# GATE_DRIVER_BOARD.net
KiCad netlist of a schematic drawn in Altium Designer
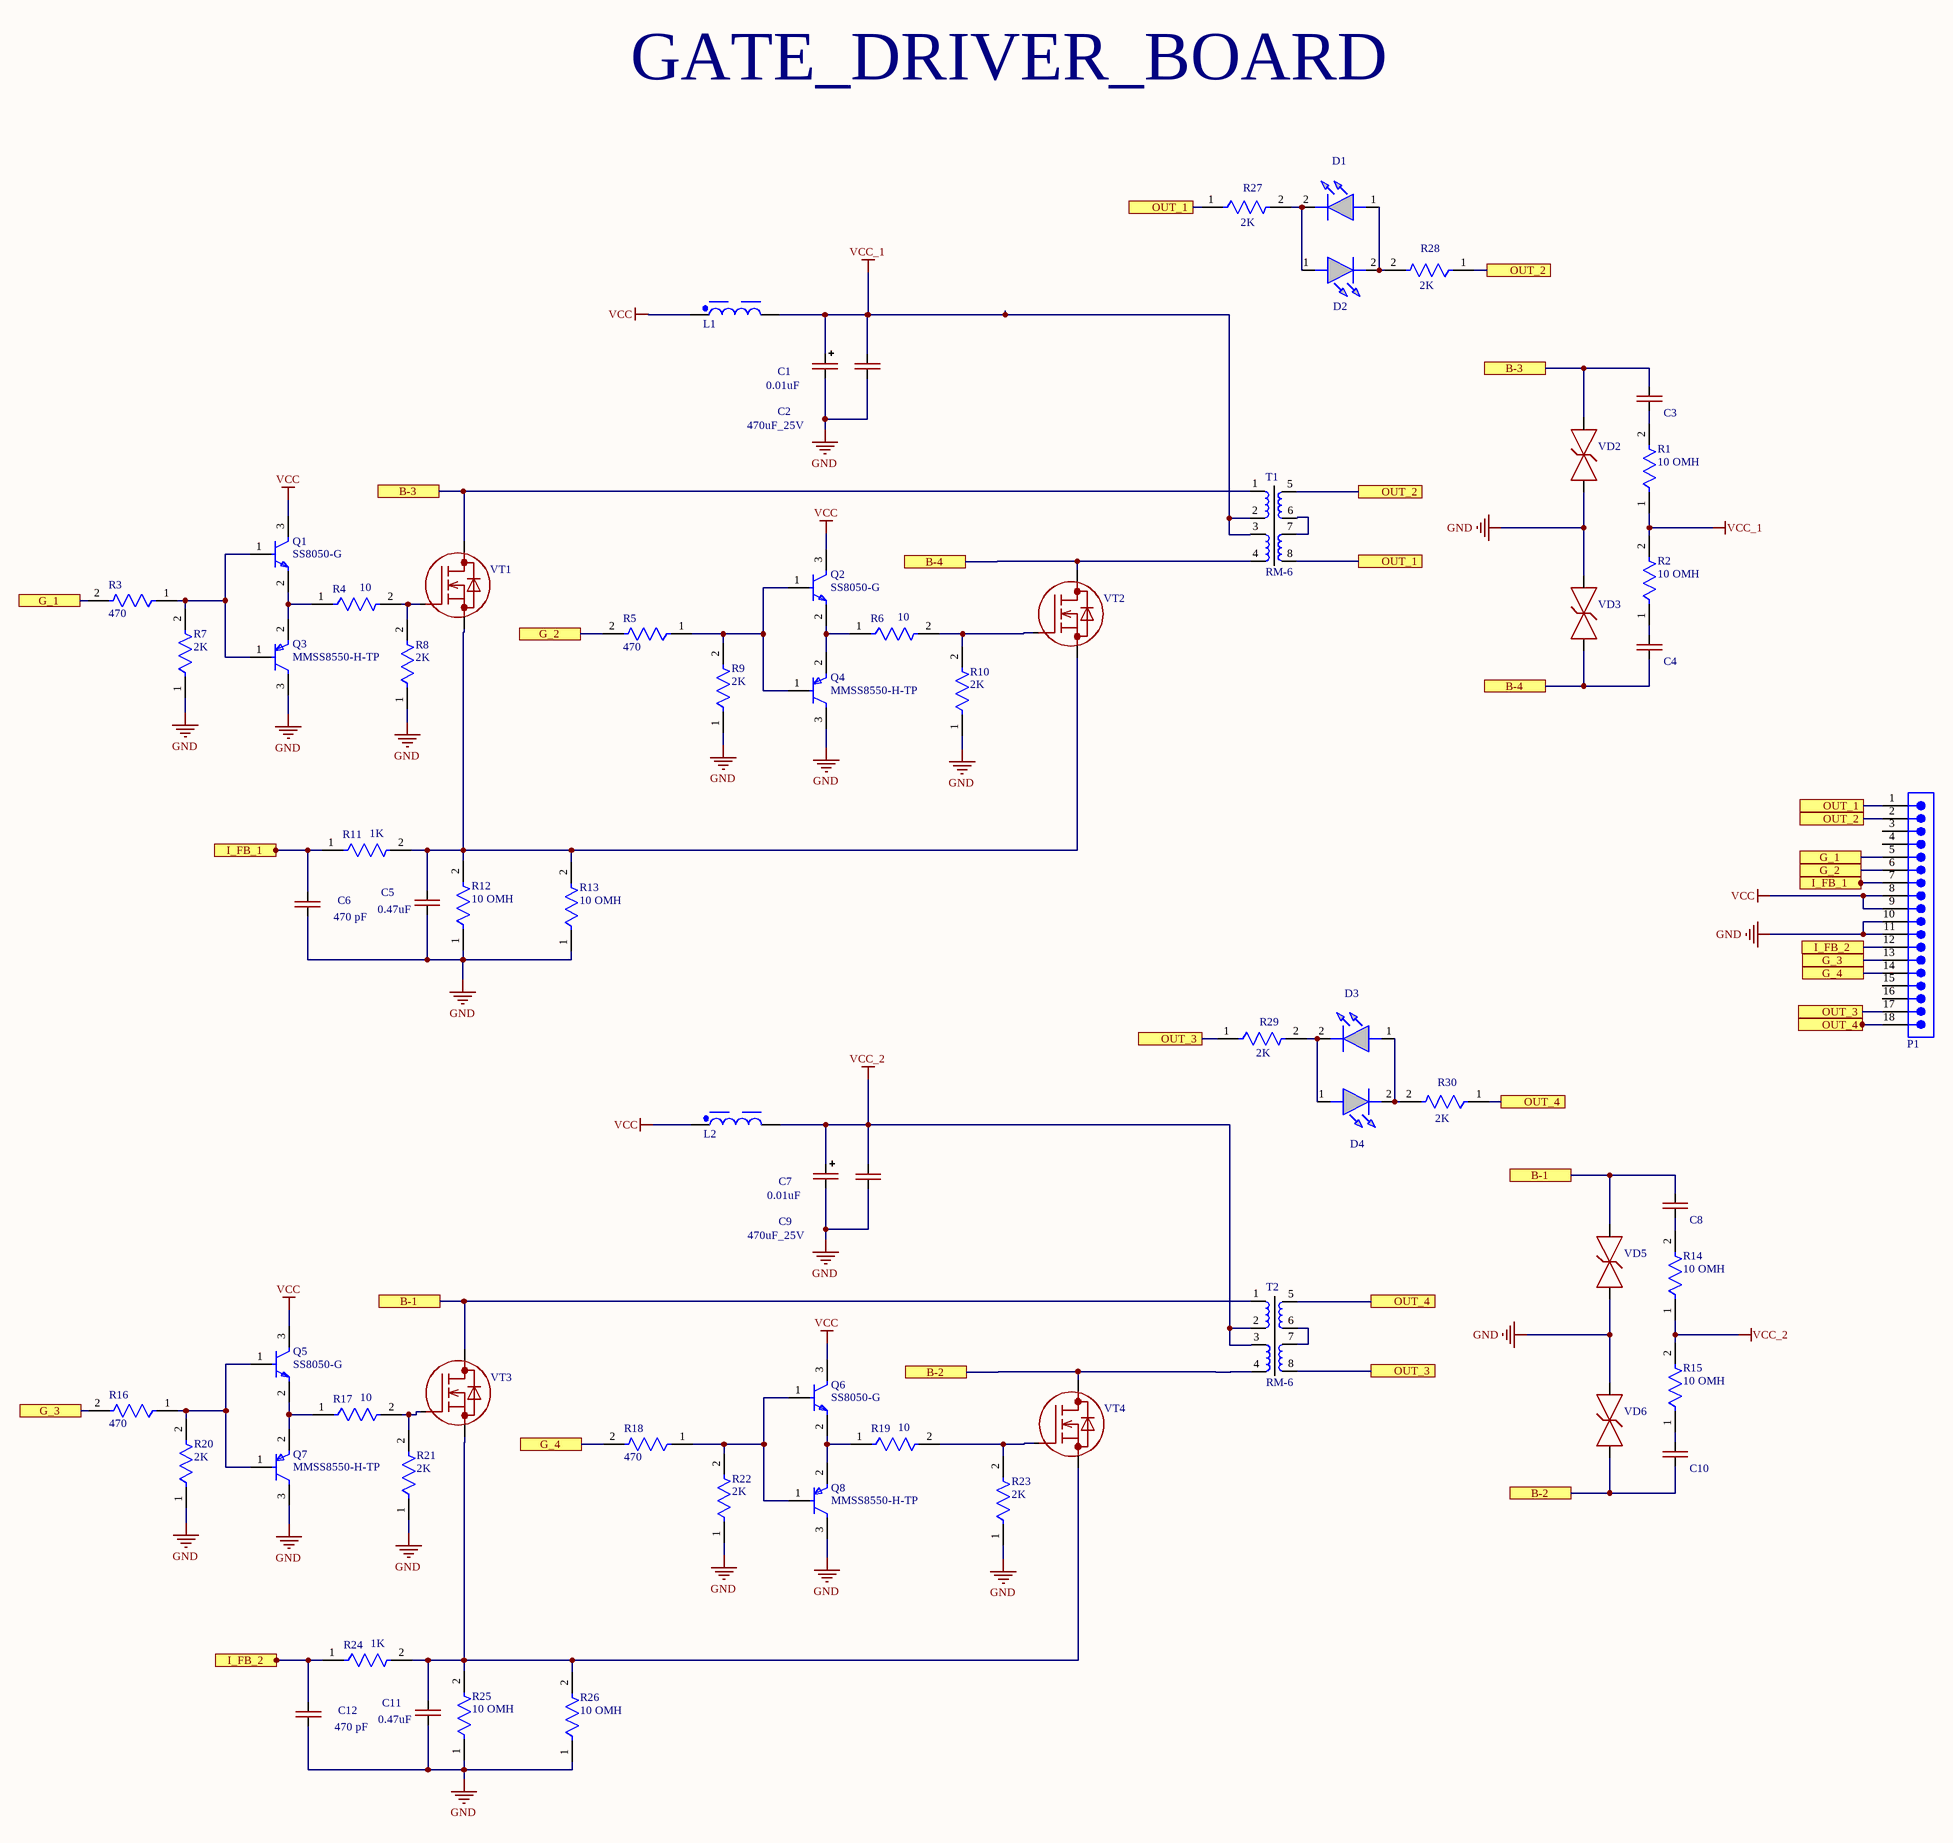
[diagram p0: GATE_DRIVER_BOARD.SchDoc]

(export (version "E")
  (design (tool "Eeschema 10.0.6"))
  (components
    (comp (ref "C1")
      (value "0.01uF")
      (footprint "CAP-0805")
      (libsource (lib "PASSIVE_COMPONENTS") (part "CAP-NON-POLAR"))
    )
    (comp (ref "C2")
      (value "470uF_25V")
      (footprint "CAP_SMD_Size_G")
      (libsource (lib "PASSIVE_COMPONENTS") (part "CAP-POLAR"))
    )
    (comp (ref "C3")
      (value "CAP-V")
      (footprint "CAP-V")
      (libsource (lib "PASSIVE_COMPONENTS") (part "CAP-V"))
    )
    (comp (ref "C4")
      (value "CAP-V")
      (footprint "CAP-V")
      (libsource (lib "PASSIVE_COMPONENTS") (part "CAP-V"))
    )
    (comp (ref "C5")
      (value "0.47uF")
      (footprint "CAP-0805")
      (libsource (lib "PASSIVE_COMPONENTS") (part "CAP-NON-POLAR"))
    )
    (comp (ref "C6")
      (value "470 pF")
      (footprint "CAP-0805")
      (libsource (lib "PASSIVE_COMPONENTS") (part "CAP-NON-POLAR"))
    )
    (comp (ref "C7")
      (value "0.01uF")
      (footprint "CAP-0805")
      (libsource (lib "PASSIVE_COMPONENTS") (part "CAP-NON-POLAR"))
    )
    (comp (ref "C8")
      (value "CAP-V")
      (footprint "CAP-V")
      (libsource (lib "PASSIVE_COMPONENTS") (part "CAP-V"))
    )
    (comp (ref "C9")
      (value "470uF_25V")
      (footprint "CAP_SMD_Size_G")
      (libsource (lib "PASSIVE_COMPONENTS") (part "CAP-POLAR"))
    )
    (comp (ref "C10")
      (value "CAP-V")
      (footprint "CAP-V")
      (libsource (lib "PASSIVE_COMPONENTS") (part "CAP-V"))
    )
    (comp (ref "C11")
      (value "0.47uF")
      (footprint "CAP-0805")
      (libsource (lib "PASSIVE_COMPONENTS") (part "CAP-NON-POLAR"))
    )
    (comp (ref "C12")
      (value "470 pF")
      (footprint "CAP-0805")
      (libsource (lib "PASSIVE_COMPONENTS") (part "CAP-NON-POLAR"))
    )
    (comp (ref "D1")
      (value "151031YS06000")
      (footprint "LED_RED")
      (description "WURTH ELEKTRONIK - 151031YS06000 - LED, Yellow, Through Hole, T-1 (3mm), 30 mA, 2 V, 590 nm")
      (fields (field (name "MOUSER PART NUMBER") "710-151031YS06000"))
      (libsource (lib "Optic-LED") (part "LED"))
    )
    (comp (ref "D2")
      (value "151031YS06000")
      (footprint "LED_RED")
      (description "WURTH ELEKTRONIK - 151031YS06000 - LED, Yellow, Through Hole, T-1 (3mm), 30 mA, 2 V, 590 nm")
      (fields (field (name "MOUSER PART NUMBER") "710-151031YS06000"))
      (libsource (lib "Optic-LED") (part "LED"))
    )
    (comp (ref "D3")
      (value "151031YS06000")
      (footprint "LED_RED")
      (description "WURTH ELEKTRONIK - 151031YS06000 - LED, Yellow, Through Hole, T-1 (3mm), 30 mA, 2 V, 590 nm")
      (fields (field (name "MOUSER PART NUMBER") "710-151031YS06000"))
      (libsource (lib "Optic-LED") (part "LED"))
    )
    (comp (ref "D4")
      (value "151031YS06000")
      (footprint "LED_RED")
      (description "WURTH ELEKTRONIK - 151031YS06000 - LED, Yellow, Through Hole, T-1 (3mm), 30 mA, 2 V, 590 nm")
      (fields (field (name "MOUSER PART NUMBER") "710-151031YS06000"))
      (libsource (lib "Optic-LED") (part "LED"))
    )
    (comp (ref "L1")
      (value "390µH, 0.38A")
      (footprint "WE-PD2_7850")
      (description "WE-PD2 SMT Power Inductor, size 7850, 390µH, 0.38A, 1.77Ω")
      (fields
        (field (name "MANUFACTURER PART NUMBER") "744775239")
        (field (name "MANUFACTURER") "Wurth Elektronik")
      )
      (libsource (lib "WE-PD2 (rev22d)") (part "744775239"))
    )
    (comp (ref "L2")
      (value "390µH, 0.38A")
      (footprint "WE-PD2_7850")
      (description "WE-PD2 SMT Power Inductor, size 7850, 390µH, 0.38A, 1.77Ω")
      (fields
        (field (name "MANUFACTURER PART NUMBER") "744775239")
        (field (name "MANUFACTURER") "Wurth Elektronik")
      )
      (libsource (lib "WE-PD2 (rev22d)") (part "744775239"))
    )
    (comp (ref "P1")
      (value "61301811021")
      (footprint "61301811021")
      (description "WR-PHD Pin Header, THT, Angled, pitch 2.54mm, 1 Row, 18P")
      (fields (field (name "MANUFACTURER") "Wurth Elektronik"))
      (libsource (lib "Altium_WR-PHD (rev22b)") (part "61301811021"))
    )
    (comp (ref "Q1")
      (value "SS8050-G")
      (footprint "FP-SS8050-G-MFG")
      (description "NPN TRANSISTOR 1.5A 40V SOT-23 R")
      (libsource (lib "Altium Content Vault") (part "2a1388f82443b098dcd57d24ac7632d"))
    )
    (comp (ref "Q2")
      (value "SS8050-G")
      (footprint "FP-SS8050-G-MFG")
      (description "NPN TRANSISTOR 1.5A 40V SOT-23 R")
      (libsource (lib "Altium Content Vault") (part "2a1388f82443b098dcd57d24ac7632d"))
    )
    (comp (ref "Q3")
      (value "MMSS8550-H-TP")
      (footprint "FP-SOT-23-IPC_B")
      (description "TRANS PNP 25V 1.5A SOT23")
      (libsource (lib "Altium Content Vault") (part "0e8486ed3b47d9c69b8404ba87cf0f7"))
    )
    (comp (ref "Q4")
      (value "MMSS8550-H-TP")
      (footprint "FP-SOT-23-IPC_B")
      (description "TRANS PNP 25V 1.5A SOT23")
      (libsource (lib "Altium Content Vault") (part "0e8486ed3b47d9c69b8404ba87cf0f7"))
    )
    (comp (ref "Q5")
      (value "SS8050-G")
      (footprint "FP-SS8050-G-MFG")
      (description "NPN TRANSISTOR 1.5A 40V SOT-23 R")
      (libsource (lib "Altium Content Vault") (part "2a1388f82443b098dcd57d24ac7632d"))
    )
    (comp (ref "Q6")
      (value "SS8050-G")
      (footprint "FP-SS8050-G-MFG")
      (description "NPN TRANSISTOR 1.5A 40V SOT-23 R")
      (libsource (lib "Altium Content Vault") (part "2a1388f82443b098dcd57d24ac7632d"))
    )
    (comp (ref "Q7")
      (value "MMSS8550-H-TP")
      (footprint "FP-SOT-23-IPC_B")
      (description "TRANS PNP 25V 1.5A SOT23")
      (libsource (lib "Altium Content Vault") (part "0e8486ed3b47d9c69b8404ba87cf0f7"))
    )
    (comp (ref "Q8")
      (value "MMSS8550-H-TP")
      (footprint "FP-SOT-23-IPC_B")
      (description "TRANS PNP 25V 1.5A SOT23")
      (libsource (lib "Altium Content Vault") (part "0e8486ed3b47d9c69b8404ba87cf0f7"))
    )
    (comp (ref "R1")
      (value "10 OMH")
      (footprint "RES-1206")
      (libsource (lib "PASSIVE_COMPONENTS") (part "RES-CONST"))
    )
    (comp (ref "R2")
      (value "10 OMH")
      (footprint "RES-1206")
      (libsource (lib "PASSIVE_COMPONENTS") (part "RES-CONST"))
    )
    (comp (ref "R3")
      (value "470")
      (footprint "RES-0805")
      (libsource (lib "PASSIVE_COMPONENTS") (part "RES-CONST"))
    )
    (comp (ref "R4")
      (value "10")
      (footprint "RES-0805")
      (libsource (lib "PASSIVE_COMPONENTS") (part "RES-CONST"))
    )
    (comp (ref "R5")
      (value "470")
      (footprint "RES-0805")
      (libsource (lib "PASSIVE_COMPONENTS") (part "RES-CONST"))
    )
    (comp (ref "R6")
      (value "10")
      (footprint "RES-0805")
      (libsource (lib "PASSIVE_COMPONENTS") (part "RES-CONST"))
    )
    (comp (ref "R7")
      (value "2K")
      (footprint "RES-0805")
      (libsource (lib "PASSIVE_COMPONENTS") (part "RES-CONST"))
    )
    (comp (ref "R8")
      (value "2K")
      (footprint "RES-0805")
      (libsource (lib "PASSIVE_COMPONENTS") (part "RES-CONST"))
    )
    (comp (ref "R9")
      (value "2K")
      (footprint "RES-0805")
      (libsource (lib "PASSIVE_COMPONENTS") (part "RES-CONST"))
    )
    (comp (ref "R10")
      (value "2K")
      (footprint "RES-0805")
      (libsource (lib "PASSIVE_COMPONENTS") (part "RES-CONST"))
    )
    (comp (ref "R11")
      (value "1K")
      (footprint "RES-0805")
      (libsource (lib "PASSIVE_COMPONENTS") (part "RES-CONST"))
    )
    (comp (ref "R12")
      (value "10 OMH")
      (footprint "RES-2512")
      (libsource (lib "PASSIVE_COMPONENTS") (part "RES-CONST"))
    )
    (comp (ref "R13")
      (value "10 OMH")
      (footprint "RES-2512")
      (libsource (lib "PASSIVE_COMPONENTS") (part "RES-CONST"))
    )
    (comp (ref "R14")
      (value "10 OMH")
      (footprint "RES-1206")
      (libsource (lib "PASSIVE_COMPONENTS") (part "RES-CONST"))
    )
    (comp (ref "R15")
      (value "10 OMH")
      (footprint "RES-1206")
      (libsource (lib "PASSIVE_COMPONENTS") (part "RES-CONST"))
    )
    (comp (ref "R16")
      (value "470")
      (footprint "RES-0805")
      (libsource (lib "PASSIVE_COMPONENTS") (part "RES-CONST"))
    )
    (comp (ref "R17")
      (value "10")
      (footprint "RES-0805")
      (libsource (lib "PASSIVE_COMPONENTS") (part "RES-CONST"))
    )
    (comp (ref "R18")
      (value "470")
      (footprint "RES-0805")
      (libsource (lib "PASSIVE_COMPONENTS") (part "RES-CONST"))
    )
    (comp (ref "R19")
      (value "10")
      (footprint "RES-0805")
      (libsource (lib "PASSIVE_COMPONENTS") (part "RES-CONST"))
    )
    (comp (ref "R20")
      (value "2K")
      (footprint "RES-0805")
      (libsource (lib "PASSIVE_COMPONENTS") (part "RES-CONST"))
    )
    (comp (ref "R21")
      (value "2K")
      (footprint "RES-0805")
      (libsource (lib "PASSIVE_COMPONENTS") (part "RES-CONST"))
    )
    (comp (ref "R22")
      (value "2K")
      (footprint "RES-0805")
      (libsource (lib "PASSIVE_COMPONENTS") (part "RES-CONST"))
    )
    (comp (ref "R23")
      (value "2K")
      (footprint "RES-0805")
      (libsource (lib "PASSIVE_COMPONENTS") (part "RES-CONST"))
    )
    (comp (ref "R24")
      (value "1K")
      (footprint "RES-0805")
      (libsource (lib "PASSIVE_COMPONENTS") (part "RES-CONST"))
    )
    (comp (ref "R25")
      (value "10 OMH")
      (footprint "RES-2512")
      (libsource (lib "PASSIVE_COMPONENTS") (part "RES-CONST"))
    )
    (comp (ref "R26")
      (value "10 OMH")
      (footprint "RES-2512")
      (libsource (lib "PASSIVE_COMPONENTS") (part "RES-CONST"))
    )
    (comp (ref "R27")
      (value "2K")
      (footprint "RES-0805")
      (description "10K")
      (libsource (lib "PASSIVE_COMPONENTS") (part "RES-CONST"))
    )
    (comp (ref "R28")
      (value "2K")
      (footprint "RES-0805")
      (description "10K")
      (libsource (lib "PASSIVE_COMPONENTS") (part "RES-CONST"))
    )
    (comp (ref "R29")
      (value "2K")
      (footprint "RES-0805")
      (description "10K")
      (libsource (lib "PASSIVE_COMPONENTS") (part "RES-CONST"))
    )
    (comp (ref "R30")
      (value "2K")
      (footprint "RES-0805")
      (description "10K")
      (libsource (lib "PASSIVE_COMPONENTS") (part "RES-CONST"))
    )
    (comp (ref "T1")
      (value "RM-6")
      (footprint "TRANS_RM6")
      (libsource (lib "Transformers") (part "RM_6_12-12-18-18"))
    )
    (comp (ref "T2")
      (value "RM-6")
      (footprint "TRANS_RM6")
      (libsource (lib "Transformers") (part "RM_6_12-12-18-18"))
    )
    (comp (ref "VD2")
      (value "Suppressor")
      (footprint "P6KE350CA")
      (libsource (lib "Diodes") (part "Suppressor"))
    )
    (comp (ref "VD3")
      (value "Suppressor")
      (footprint "P6KE350CA")
      (libsource (lib "Diodes") (part "Suppressor"))
    )
    (comp (ref "VD5")
      (value "Suppressor")
      (footprint "P6KE350CA")
      (libsource (lib "Diodes") (part "Suppressor"))
    )
    (comp (ref "VD6")
      (value "Suppressor")
      (footprint "P6KE350CA")
      (libsource (lib "Diodes") (part "Suppressor"))
    )
    (comp (ref "VT1")
      (value "MOSFET-N-GDS")
      (footprint "TO-220-5")
      (libsource (lib "AOD514") (part "MOSFET-N-GDS"))
    )
    (comp (ref "VT2")
      (value "MOSFET-N-GDS")
      (footprint "TO-220-5")
      (libsource (lib "AOD514") (part "MOSFET-N-GDS"))
    )
    (comp (ref "VT3")
      (value "MOSFET-N-GDS")
      (footprint "TO-220-5")
      (libsource (lib "AOD514") (part "MOSFET-N-GDS"))
    )
    (comp (ref "VT4")
      (value "MOSFET-N-GDS")
      (footprint "TO-220-5")
      (libsource (lib "AOD514") (part "MOSFET-N-GDS"))
    )
  )
  (nets
    (net (code "1") (name "/B-1") (class "Default")
      (node (ref "C8") (pin "2") (pinfunction "2_2") (pintype "passive"))
      (node (ref "T2") (pin "1") (pinfunction "1_1") (pintype "passive"))
      (node (ref "VD5") (pin "2") (pinfunction "A_2") (pintype "passive"))
      (node (ref "VT3") (pin "2") (pinfunction "D_2") (pintype "passive"))
    )
    (net (code "2") (name "/B-2") (class "Default")
      (node (ref "C10") (pin "1") (pinfunction "1_1") (pintype "passive"))
      (node (ref "T2") (pin "4") (pinfunction "4_4") (pintype "passive"))
      (node (ref "VD6") (pin "1") (pinfunction "C_1") (pintype "passive"))
      (node (ref "VT4") (pin "2") (pinfunction "D_2") (pintype "passive"))
    )
    (net (code "3") (name "/B-3") (class "Default")
      (node (ref "C3") (pin "2") (pinfunction "2_2") (pintype "passive"))
      (node (ref "T1") (pin "1") (pinfunction "1_1") (pintype "passive"))
      (node (ref "VD2") (pin "2") (pinfunction "A_2") (pintype "passive"))
      (node (ref "VT1") (pin "2") (pinfunction "D_2") (pintype "passive"))
    )
    (net (code "4") (name "/B-4") (class "Default")
      (node (ref "C4") (pin "1") (pinfunction "1_1") (pintype "passive"))
      (node (ref "T1") (pin "4") (pinfunction "4_4") (pintype "passive"))
      (node (ref "VD3") (pin "1") (pinfunction "C_1") (pintype "passive"))
      (node (ref "VT2") (pin "2") (pinfunction "D_2") (pintype "passive"))
    )
    (net (code "5") (name "/G_1") (class "Default")
      (node (ref "P1") (pin "5") (pinfunction "5_5") (pintype "passive"))
      (node (ref "R3") (pin "2") (pinfunction "2_2") (pintype "passive"))
    )
    (net (code "6") (name "/G_2") (class "Default")
      (node (ref "P1") (pin "6") (pinfunction "6_6") (pintype "passive"))
      (node (ref "R5") (pin "2") (pinfunction "2_2") (pintype "passive"))
    )
    (net (code "7") (name "/G_3") (class "Default")
      (node (ref "P1") (pin "13") (pinfunction "13_13") (pintype "passive"))
      (node (ref "R16") (pin "2") (pinfunction "2_2") (pintype "passive"))
    )
    (net (code "8") (name "/G_4") (class "Default")
      (node (ref "P1") (pin "14") (pinfunction "14_14") (pintype "passive"))
      (node (ref "R18") (pin "2") (pinfunction "2_2") (pintype "passive"))
    )
    (net (code "9") (name "/I_FB_1") (class "Default")
      (node (ref "C6") (pin "2") (pinfunction "2_2") (pintype "passive"))
      (node (ref "P1") (pin "7") (pinfunction "7_7") (pintype "passive"))
      (node (ref "R11") (pin "1") (pinfunction "1_1") (pintype "passive"))
    )
    (net (code "10") (name "/I_FB_2") (class "Default")
      (node (ref "C12") (pin "2") (pinfunction "2_2") (pintype "passive"))
      (node (ref "P1") (pin "12") (pinfunction "12_12") (pintype "passive"))
      (node (ref "R24") (pin "1") (pinfunction "1_1") (pintype "passive"))
    )
    (net (code "11") (name "/OUT_1") (class "Default")
      (node (ref "P1") (pin "1") (pinfunction "1_1") (pintype "passive"))
      (node (ref "R27") (pin "1") (pinfunction "1_1") (pintype "passive"))
      (node (ref "T1") (pin "8") (pinfunction "8_8") (pintype "passive"))
    )
    (net (code "12") (name "/OUT_2") (class "Default")
      (node (ref "P1") (pin "2") (pinfunction "2_2") (pintype "passive"))
      (node (ref "R28") (pin "1") (pinfunction "1_1") (pintype "passive"))
      (node (ref "T1") (pin "5") (pinfunction "5_5") (pintype "passive"))
    )
    (net (code "13") (name "/OUT_3") (class "Default")
      (node (ref "P1") (pin "17") (pinfunction "17_17") (pintype "passive"))
      (node (ref "R29") (pin "1") (pinfunction "1_1") (pintype "passive"))
      (node (ref "T2") (pin "8") (pinfunction "8_8") (pintype "passive"))
    )
    (net (code "14") (name "/OUT_4") (class "Default")
      (node (ref "P1") (pin "18") (pinfunction "18_18") (pintype "passive"))
      (node (ref "R30") (pin "1") (pinfunction "1_1") (pintype "passive"))
      (node (ref "T2") (pin "5") (pinfunction "5_5") (pintype "passive"))
    )
    (net (code "15") (name "GND") (class "Default")
      (node (ref "C1") (pin "1") (pinfunction "1_1") (pintype "passive"))
      (node (ref "C11") (pin "1") (pinfunction "1_1") (pintype "passive"))
      (node (ref "C12") (pin "1") (pinfunction "1_1") (pintype "passive"))
      (node (ref "C2") (pin "2") (pinfunction "-_2") (pintype "passive"))
      (node (ref "C5") (pin "1") (pinfunction "1_1") (pintype "passive"))
      (node (ref "C6") (pin "1") (pinfunction "1_1") (pintype "passive"))
      (node (ref "C7") (pin "1") (pinfunction "1_1") (pintype "passive"))
      (node (ref "C9") (pin "2") (pinfunction "-_2") (pintype "passive"))
      (node (ref "P1") (pin "10") (pinfunction "10_10") (pintype "passive"))
      (node (ref "P1") (pin "11") (pinfunction "11_11") (pintype "passive"))
      (node (ref "Q3") (pin "3") (pinfunction "C_3") (pintype "passive"))
      (node (ref "Q4") (pin "3") (pinfunction "C_3") (pintype "passive"))
      (node (ref "Q7") (pin "3") (pinfunction "C_3") (pintype "passive"))
      (node (ref "Q8") (pin "3") (pinfunction "C_3") (pintype "passive"))
      (node (ref "R10") (pin "1") (pinfunction "1_1") (pintype "passive"))
      (node (ref "R12") (pin "1") (pinfunction "1_1") (pintype "passive"))
      (node (ref "R13") (pin "1") (pinfunction "1_1") (pintype "passive"))
      (node (ref "R20") (pin "1") (pinfunction "1_1") (pintype "passive"))
      (node (ref "R21") (pin "1") (pinfunction "1_1") (pintype "passive"))
      (node (ref "R22") (pin "1") (pinfunction "1_1") (pintype "passive"))
      (node (ref "R23") (pin "1") (pinfunction "1_1") (pintype "passive"))
      (node (ref "R25") (pin "1") (pinfunction "1_1") (pintype "passive"))
      (node (ref "R26") (pin "1") (pinfunction "1_1") (pintype "passive"))
      (node (ref "R7") (pin "1") (pinfunction "1_1") (pintype "passive"))
      (node (ref "R8") (pin "1") (pinfunction "1_1") (pintype "passive"))
      (node (ref "R9") (pin "1") (pinfunction "1_1") (pintype "passive"))
      (node (ref "VD2") (pin "1") (pinfunction "C_1") (pintype "passive"))
      (node (ref "VD3") (pin "2") (pinfunction "A_2") (pintype "passive"))
      (node (ref "VD5") (pin "1") (pinfunction "C_1") (pintype "passive"))
      (node (ref "VD6") (pin "2") (pinfunction "A_2") (pintype "passive"))
    )
    (net (code "16") (name "Net-(C3-Pad1)") (class "Default")
      (node (ref "C3") (pin "1") (pinfunction "1_1") (pintype "passive"))
      (node (ref "R1") (pin "2") (pinfunction "2_2") (pintype "passive"))
    )
    (net (code "17") (name "Net-(C4-Pad2)") (class "Default")
      (node (ref "C4") (pin "2") (pinfunction "2_2") (pintype "passive"))
      (node (ref "R2") (pin "1") (pinfunction "1_1") (pintype "passive"))
    )
    (net (code "18") (name "Net-(C8-Pad1)") (class "Default")
      (node (ref "C8") (pin "1") (pinfunction "1_1") (pintype "passive"))
      (node (ref "R14") (pin "2") (pinfunction "2_2") (pintype "passive"))
    )
    (net (code "19") (name "Net-(C10-Pad2)") (class "Default")
      (node (ref "C10") (pin "2") (pinfunction "2_2") (pintype "passive"))
      (node (ref "R15") (pin "1") (pinfunction "1_1") (pintype "passive"))
    )
    (net (code "20") (name "Net-(D1-A)") (class "Default")
      (node (ref "D1") (pin "1") (pinfunction "A_1") (pintype "passive"))
      (node (ref "D2") (pin "2") (pinfunction "K_2") (pintype "passive"))
      (node (ref "R28") (pin "2") (pinfunction "2_2") (pintype "passive"))
    )
    (net (code "21") (name "Net-(D1-K)") (class "Default")
      (node (ref "D1") (pin "2") (pinfunction "K_2") (pintype "passive"))
      (node (ref "D2") (pin "1") (pinfunction "A_1") (pintype "passive"))
      (node (ref "R27") (pin "2") (pinfunction "2_2") (pintype "passive"))
    )
    (net (code "22") (name "Net-(D3-A)") (class "Default")
      (node (ref "D3") (pin "1") (pinfunction "A_1") (pintype "passive"))
      (node (ref "D4") (pin "2") (pinfunction "K_2") (pintype "passive"))
      (node (ref "R30") (pin "2") (pinfunction "2_2") (pintype "passive"))
    )
    (net (code "23") (name "Net-(D3-K)") (class "Default")
      (node (ref "D3") (pin "2") (pinfunction "K_2") (pintype "passive"))
      (node (ref "D4") (pin "1") (pinfunction "A_1") (pintype "passive"))
      (node (ref "R29") (pin "2") (pinfunction "2_2") (pintype "passive"))
    )
    (net (code "24") (name "Net-(Q1-B)") (class "Default")
      (node (ref "Q1") (pin "1") (pinfunction "B_1") (pintype "passive"))
      (node (ref "Q3") (pin "1") (pinfunction "B_1") (pintype "passive"))
      (node (ref "R3") (pin "1") (pinfunction "1_1") (pintype "passive"))
      (node (ref "R7") (pin "2") (pinfunction "2_2") (pintype "passive"))
    )
    (net (code "25") (name "Net-(Q1-E)") (class "Default")
      (node (ref "Q1") (pin "2") (pinfunction "E_2") (pintype "passive"))
      (node (ref "Q3") (pin "2") (pinfunction "E_2") (pintype "passive"))
      (node (ref "R4") (pin "1") (pinfunction "1_1") (pintype "passive"))
    )
    (net (code "26") (name "Net-(Q2-B)") (class "Default")
      (node (ref "Q2") (pin "1") (pinfunction "B_1") (pintype "passive"))
      (node (ref "Q4") (pin "1") (pinfunction "B_1") (pintype "passive"))
      (node (ref "R5") (pin "1") (pinfunction "1_1") (pintype "passive"))
      (node (ref "R9") (pin "2") (pinfunction "2_2") (pintype "passive"))
    )
    (net (code "27") (name "Net-(Q2-E)") (class "Default")
      (node (ref "Q2") (pin "2") (pinfunction "E_2") (pintype "passive"))
      (node (ref "Q4") (pin "2") (pinfunction "E_2") (pintype "passive"))
      (node (ref "R6") (pin "1") (pinfunction "1_1") (pintype "passive"))
    )
    (net (code "28") (name "Net-(Q5-B)") (class "Default")
      (node (ref "Q5") (pin "1") (pinfunction "B_1") (pintype "passive"))
      (node (ref "Q7") (pin "1") (pinfunction "B_1") (pintype "passive"))
      (node (ref "R16") (pin "1") (pinfunction "1_1") (pintype "passive"))
      (node (ref "R20") (pin "2") (pinfunction "2_2") (pintype "passive"))
    )
    (net (code "29") (name "Net-(Q5-E)") (class "Default")
      (node (ref "Q5") (pin "2") (pinfunction "E_2") (pintype "passive"))
      (node (ref "Q7") (pin "2") (pinfunction "E_2") (pintype "passive"))
      (node (ref "R17") (pin "1") (pinfunction "1_1") (pintype "passive"))
    )
    (net (code "30") (name "Net-(Q6-B)") (class "Default")
      (node (ref "Q6") (pin "1") (pinfunction "B_1") (pintype "passive"))
      (node (ref "Q8") (pin "1") (pinfunction "B_1") (pintype "passive"))
      (node (ref "R18") (pin "1") (pinfunction "1_1") (pintype "passive"))
      (node (ref "R22") (pin "2") (pinfunction "2_2") (pintype "passive"))
    )
    (net (code "31") (name "Net-(Q6-E)") (class "Default")
      (node (ref "Q6") (pin "2") (pinfunction "E_2") (pintype "passive"))
      (node (ref "Q8") (pin "2") (pinfunction "E_2") (pintype "passive"))
      (node (ref "R19") (pin "1") (pinfunction "1_1") (pintype "passive"))
    )
    (net (code "32") (name "Net-(T1-Pad6)") (class "Default")
      (node (ref "T1") (pin "6") (pinfunction "6_6") (pintype "passive"))
      (node (ref "T1") (pin "7") (pinfunction "7_7") (pintype "passive"))
    )
    (net (code "33") (name "Net-(T2-Pad6)") (class "Default")
      (node (ref "T2") (pin "6") (pinfunction "6_6") (pintype "passive"))
      (node (ref "T2") (pin "7") (pinfunction "7_7") (pintype "passive"))
    )
    (net (code "34") (name "Net-(VT1-G)") (class "Default")
      (node (ref "R4") (pin "2") (pinfunction "2_2") (pintype "passive"))
      (node (ref "R8") (pin "2") (pinfunction "2_2") (pintype "passive"))
      (node (ref "VT1") (pin "1") (pinfunction "G_1") (pintype "passive"))
    )
    (net (code "35") (name "Net-(VT1-S)") (class "Default")
      (node (ref "C5") (pin "2") (pinfunction "2_2") (pintype "passive"))
      (node (ref "R11") (pin "2") (pinfunction "2_2") (pintype "passive"))
      (node (ref "R12") (pin "2") (pinfunction "2_2") (pintype "passive"))
      (node (ref "R13") (pin "2") (pinfunction "2_2") (pintype "passive"))
      (node (ref "VT1") (pin "3") (pinfunction "S_3") (pintype "passive"))
      (node (ref "VT2") (pin "3") (pinfunction "S_3") (pintype "passive"))
    )
    (net (code "36") (name "Net-(VT2-G)") (class "Default")
      (node (ref "R10") (pin "2") (pinfunction "2_2") (pintype "passive"))
      (node (ref "R6") (pin "2") (pinfunction "2_2") (pintype "passive"))
      (node (ref "VT2") (pin "1") (pinfunction "G_1") (pintype "passive"))
    )
    (net (code "37") (name "Net-(VT3-G)") (class "Default")
      (node (ref "R17") (pin "2") (pinfunction "2_2") (pintype "passive"))
      (node (ref "R21") (pin "2") (pinfunction "2_2") (pintype "passive"))
      (node (ref "VT3") (pin "1") (pinfunction "G_1") (pintype "passive"))
    )
    (net (code "38") (name "Net-(VT3-S)") (class "Default")
      (node (ref "C11") (pin "2") (pinfunction "2_2") (pintype "passive"))
      (node (ref "R24") (pin "2") (pinfunction "2_2") (pintype "passive"))
      (node (ref "R25") (pin "2") (pinfunction "2_2") (pintype "passive"))
      (node (ref "R26") (pin "2") (pinfunction "2_2") (pintype "passive"))
      (node (ref "VT3") (pin "3") (pinfunction "S_3") (pintype "passive"))
      (node (ref "VT4") (pin "3") (pinfunction "S_3") (pintype "passive"))
    )
    (net (code "39") (name "Net-(VT4-G)") (class "Default")
      (node (ref "R19") (pin "2") (pinfunction "2_2") (pintype "passive"))
      (node (ref "R23") (pin "2") (pinfunction "2_2") (pintype "passive"))
      (node (ref "VT4") (pin "1") (pinfunction "G_1") (pintype "passive"))
    )
    (net (code "40") (name "VCC") (class "Default")
      (node (ref "L1") (pin "1") (pinfunction "1_1") (pintype "passive"))
      (node (ref "L2") (pin "1") (pinfunction "1_1") (pintype "passive"))
      (node (ref "P1") (pin "8") (pinfunction "8_8") (pintype "passive"))
      (node (ref "P1") (pin "9") (pinfunction "9_9") (pintype "passive"))
      (node (ref "Q1") (pin "3") (pinfunction "C_3") (pintype "passive"))
      (node (ref "Q2") (pin "3") (pinfunction "C_3") (pintype "passive"))
      (node (ref "Q5") (pin "3") (pinfunction "C_3") (pintype "passive"))
      (node (ref "Q6") (pin "3") (pinfunction "C_3") (pintype "passive"))
    )
    (net (code "41") (name "VCC_1") (class "Default")
      (node (ref "C1") (pin "2") (pinfunction "2_2") (pintype "passive"))
      (node (ref "C2") (pin "1") (pinfunction "+_1") (pintype "passive"))
      (node (ref "L1") (pin "2") (pinfunction "2_2") (pintype "passive"))
      (node (ref "R1") (pin "1") (pinfunction "1_1") (pintype "passive"))
      (node (ref "R2") (pin "2") (pinfunction "2_2") (pintype "passive"))
      (node (ref "T1") (pin "2") (pinfunction "2_2") (pintype "passive"))
      (node (ref "T1") (pin "3") (pinfunction "3_3") (pintype "passive"))
    )
    (net (code "42") (name "VCC_2") (class "Default")
      (node (ref "C7") (pin "2") (pinfunction "2_2") (pintype "passive"))
      (node (ref "C9") (pin "1") (pinfunction "+_1") (pintype "passive"))
      (node (ref "L2") (pin "2") (pinfunction "2_2") (pintype "passive"))
      (node (ref "R14") (pin "1") (pinfunction "1_1") (pintype "passive"))
      (node (ref "R15") (pin "2") (pinfunction "2_2") (pintype "passive"))
      (node (ref "T2") (pin "2") (pinfunction "2_2") (pintype "passive"))
      (node (ref "T2") (pin "3") (pinfunction "3_3") (pintype "passive"))
    )
    (net (code "43") (name "unconnected-(P1-Pad3)") (class "Default")
      (node (ref "P1") (pin "3") (pinfunction "3_3") (pintype "passive"))
    )
    (net (code "44") (name "unconnected-(P1-Pad4)") (class "Default")
      (node (ref "P1") (pin "4") (pinfunction "4_4") (pintype "passive"))
    )
    (net (code "45") (name "unconnected-(P1-Pad15)") (class "Default")
      (node (ref "P1") (pin "15") (pinfunction "15_15") (pintype "passive"))
    )
    (net (code "46") (name "unconnected-(P1-Pad16)") (class "Default")
      (node (ref "P1") (pin "16") (pinfunction "16_16") (pintype "passive"))
    )
  )
)
